# schematic.net
KiCad netlist of a schematic drawn in EAGLE
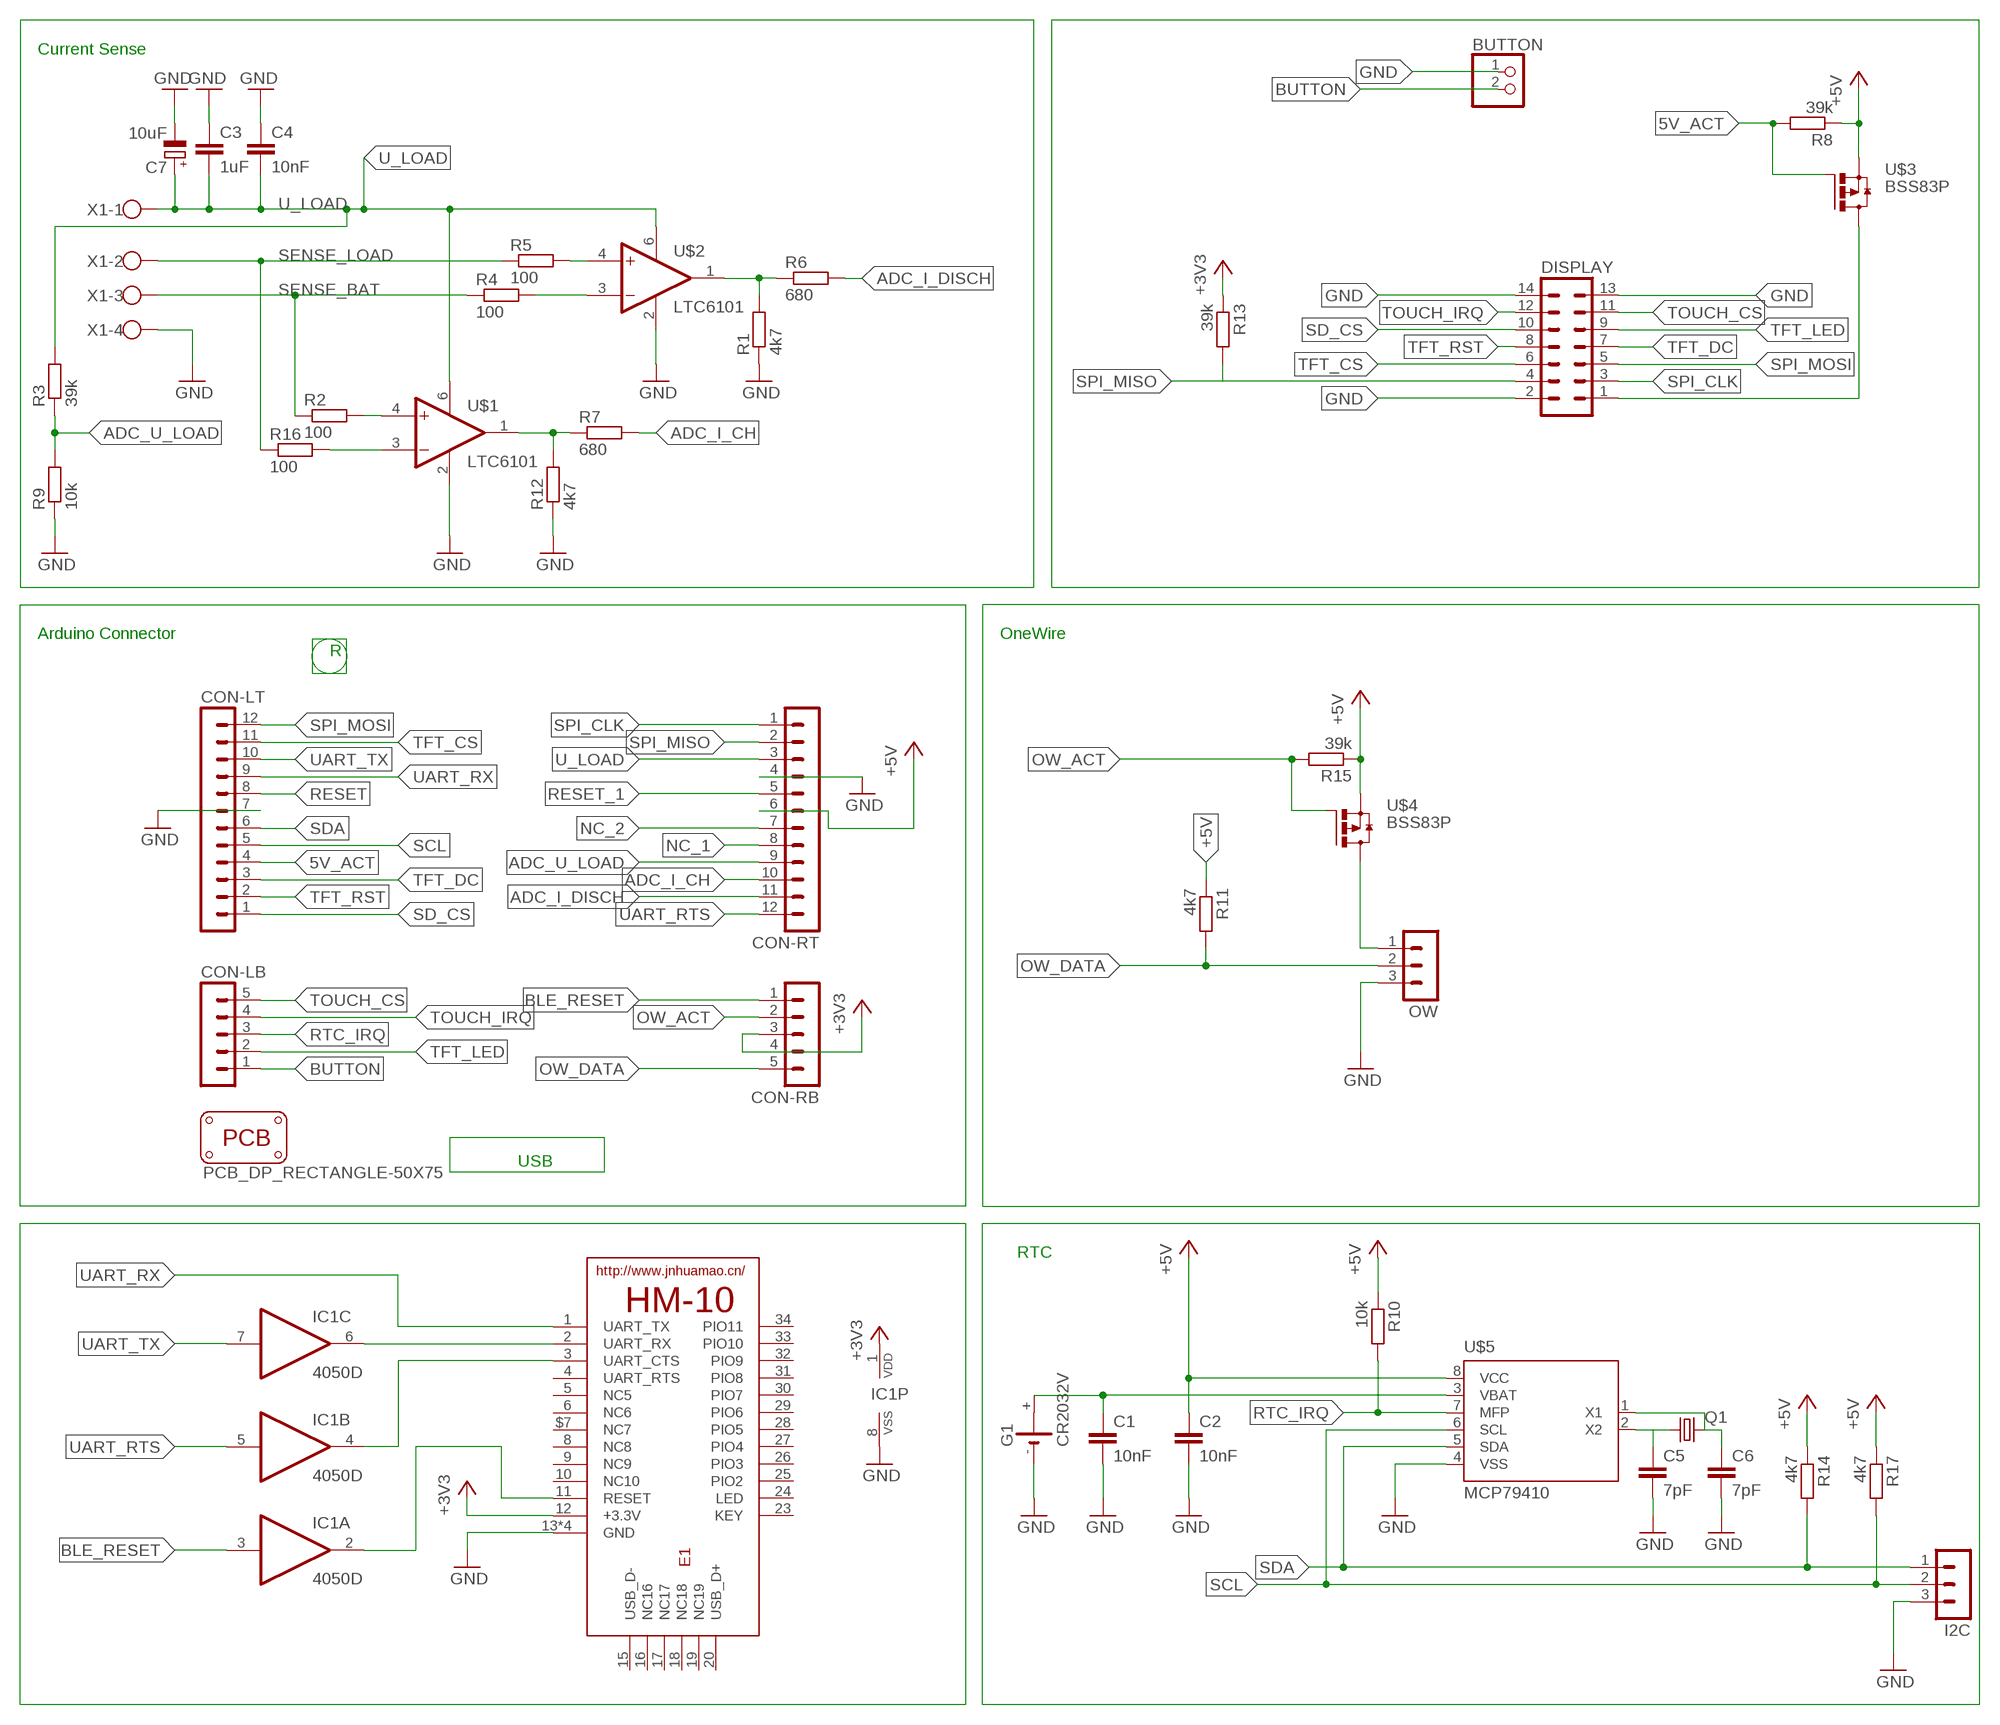
[diagram p0: schematic, sheet 1]

(export (version "E")
  (design (tool "Eeschema 10.0.6"))
  (components
    (comp (ref "BUTTON")
      (value "PINHD-1X2")
      (footprint "eagle-import:1X02")
      (libsource (lib "eagle-import") (part "PINHD-1X2"))
    )
    (comp (ref "C1")
      (value "10nF")
      (footprint "eagle-import:C1206")
      (libsource (lib "eagle-import") (part "C-EUC1206"))
    )
    (comp (ref "C2")
      (value "10nF")
      (footprint "eagle-import:C1206")
      (libsource (lib "eagle-import") (part "C-EUC1206"))
    )
    (comp (ref "C3")
      (value "1uF")
      (footprint "eagle-import:C1206")
      (libsource (lib "eagle-import") (part "C-EUC1206"))
    )
    (comp (ref "C4")
      (value "10nF")
      (footprint "eagle-import:C1206")
      (libsource (lib "eagle-import") (part "C-EUC1206"))
    )
    (comp (ref "C5")
      (value "7pF")
      (footprint "eagle-import:C1206")
      (libsource (lib "eagle-import") (part "C-EUC1206"))
    )
    (comp (ref "C6")
      (value "7pF")
      (footprint "eagle-import:C1206")
      (libsource (lib "eagle-import") (part "C-EUC1206"))
    )
    (comp (ref "C7")
      (value "10uF")
      (footprint "eagle-import:PANASONIC_B")
      (libsource (lib "eagle-import") (part "CPOL-EUB"))
    )
    (comp (ref "CON-LB")
      (value "MA05-1")
      (footprint "eagle-import:MA05-1")
      (libsource (lib "eagle-import") (part "MA05-1"))
    )
    (comp (ref "CON-LT")
      (value "MA12-1")
      (footprint "eagle-import:MA12-1")
      (libsource (lib "eagle-import") (part "MA12-1"))
    )
    (comp (ref "CON-RB")
      (value "MA05-1")
      (footprint "eagle-import:MA05-1")
      (libsource (lib "eagle-import") (part "MA05-1"))
    )
    (comp (ref "CON-RT")
      (value "MA12-1")
      (footprint "eagle-import:MA12-1")
      (libsource (lib "eagle-import") (part "MA12-1"))
    )
    (comp (ref "DISPLAY")
      (value "MA07-2")
      (footprint "eagle-import:MA07-2")
      (libsource (lib "eagle-import") (part "MA07-2"))
    )
    (comp (ref "E1")
      (value "HM-10-BOARD")
      (footprint "eagle-import:26.9X13X2.2_BOARD")
      (libsource (lib "eagle-import") (part "HM-10-BOARD"))
    )
    (comp (ref "G1")
      (value "CR2032V")
      (footprint "eagle-import:CR2032V")
      (libsource (lib "eagle-import") (part "CR2032V"))
    )
    (comp (ref "I2C")
      (value "MA03-1")
      (footprint "eagle-import:MA03-1")
      (libsource (lib "eagle-import") (part "MA03-1"))
    )
    (comp (ref "IC1")
      (value "4050D")
      (footprint "eagle-import:SO16")
      (libsource (lib "eagle-import") (part "4050D"))
    )
    (comp (ref "OW")
      (value "MA03-1")
      (footprint "eagle-import:MA03-1")
      (libsource (lib "eagle-import") (part "MA03-1"))
    )
    (comp (ref "PCB1")
      (value "PCB_DP_RECTANGLE-50X75")
      (footprint "eagle-import:DP5075_V1")
      (libsource (lib "eagle-import") (part "PCB_DP_RECTANGLE-50X75"))
    )
    (comp (ref "Q1")
      (value "CRYSTALTC26H")
      (footprint "eagle-import:TC26H")
      (libsource (lib "eagle-import") (part "CRYSTALTC26H"))
    )
    (comp (ref "R1")
      (value "4k7")
      (footprint "eagle-import:R1206")
      (libsource (lib "eagle-import") (part "R-EU_R1206"))
    )
    (comp (ref "R2")
      (value "100")
      (footprint "eagle-import:R1206")
      (libsource (lib "eagle-import") (part "R-EU_R1206"))
    )
    (comp (ref "R3")
      (value "39k")
      (footprint "eagle-import:R1206")
      (libsource (lib "eagle-import") (part "R-EU_R1206"))
    )
    (comp (ref "R4")
      (value "100")
      (footprint "eagle-import:R1206")
      (libsource (lib "eagle-import") (part "R-EU_R1206"))
    )
    (comp (ref "R5")
      (value "100")
      (footprint "eagle-import:R1206")
      (libsource (lib "eagle-import") (part "R-EU_R1206"))
    )
    (comp (ref "R6")
      (value "680")
      (footprint "eagle-import:R1206")
      (libsource (lib "eagle-import") (part "R-EU_R1206"))
    )
    (comp (ref "R7")
      (value "680")
      (footprint "eagle-import:R1206")
      (libsource (lib "eagle-import") (part "R-EU_R1206"))
    )
    (comp (ref "R8")
      (value "39k")
      (footprint "eagle-import:R1206")
      (libsource (lib "eagle-import") (part "R-EU_R1206"))
    )
    (comp (ref "R9")
      (value "10k")
      (footprint "eagle-import:R1206")
      (libsource (lib "eagle-import") (part "R-EU_R1206"))
    )
    (comp (ref "R10")
      (value "10k")
      (footprint "eagle-import:R1206")
      (libsource (lib "eagle-import") (part "R-EU_R1206"))
    )
    (comp (ref "R11")
      (value "4k7")
      (footprint "eagle-import:R1206")
      (libsource (lib "eagle-import") (part "R-EU_R1206"))
    )
    (comp (ref "R12")
      (value "4k7")
      (footprint "eagle-import:R1206")
      (libsource (lib "eagle-import") (part "R-EU_R1206"))
    )
    (comp (ref "R13")
      (value "39k")
      (footprint "eagle-import:R1206")
      (libsource (lib "eagle-import") (part "R-EU_R1206"))
    )
    (comp (ref "R14")
      (value "4k7")
      (footprint "eagle-import:R1206")
      (libsource (lib "eagle-import") (part "R-EU_R1206"))
    )
    (comp (ref "R15")
      (value "39k")
      (footprint "eagle-import:R1206")
      (libsource (lib "eagle-import") (part "R-EU_R1206"))
    )
    (comp (ref "R16")
      (value "100")
      (footprint "eagle-import:R1206")
      (libsource (lib "eagle-import") (part "R-EU_R1206"))
    )
    (comp (ref "R17")
      (value "4k7")
      (footprint "eagle-import:R1206")
      (libsource (lib "eagle-import") (part "R-EU_R1206"))
    )
    (comp (ref "U$1")
      (value "LTC6101")
      (footprint "eagle-import:TSOT23-6")
      (libsource (lib "eagle-import") (part "LTC6101"))
    )
    (comp (ref "U$2")
      (value "LTC6101")
      (footprint "eagle-import:TSOT23-6")
      (libsource (lib "eagle-import") (part "LTC6101"))
    )
    (comp (ref "U$3")
      (value "BSS83P")
      (footprint "eagle-import:SOT23")
      (libsource (lib "eagle-import") (part "BSS83P"))
    )
    (comp (ref "U$4")
      (value "BSS83P")
      (footprint "eagle-import:SOT23")
      (libsource (lib "eagle-import") (part "BSS83P"))
    )
    (comp (ref "U$5")
      (value "MCP79410")
      (footprint "eagle-import:SOIC8")
      (libsource (lib "eagle-import") (part "MCP79410"))
    )
    (comp (ref "X1")
      (value "W237-4")
      (footprint "eagle-import:W237-4")
      (libsource (lib "eagle-import") (part "W237-4"))
    )
  )
  (nets
    (net (code "1") (name "+3V3") (class "Default")
      (node (ref "CON-RB") (pin "3") (pinfunction "3_3") (pintype "passive"))
      (node (ref "CON-RB") (pin "4") (pinfunction "4_4") (pintype "passive"))
      (node (ref "E1") (pin "12") (pinfunction "+3.3V_12") (pintype "bidirectional"))
      (node (ref "IC1") (pin "1") (pinfunction "VDD_1") (pintype "power_in"))
      (node (ref "R13") (pin "1") (pinfunction "1_1") (pintype "passive"))
    )
    (net (code "2") (name "+5V") (class "Default")
      (node (ref "C2") (pin "1") (pinfunction "1_1") (pintype "passive"))
      (node (ref "CON-RT") (pin "6") (pinfunction "6_6") (pintype "passive"))
      (node (ref "R10") (pin "1") (pinfunction "1_1") (pintype "passive"))
      (node (ref "R11") (pin "1") (pinfunction "1_1") (pintype "passive"))
      (node (ref "R14") (pin "1") (pinfunction "1_1") (pintype "passive"))
      (node (ref "R15") (pin "1") (pinfunction "1_1") (pintype "passive"))
      (node (ref "R17") (pin "1") (pinfunction "1_1") (pintype "passive"))
      (node (ref "R8") (pin "1") (pinfunction "1_1") (pintype "passive"))
      (node (ref "U$3") (pin "2") (pinfunction "S_2") (pintype "passive"))
      (node (ref "U$4") (pin "2") (pinfunction "S_2") (pintype "passive"))
      (node (ref "U$5") (pin "8") (pinfunction "VCC_8") (pintype "power_in"))
    )
    (net (code "3") (name "/SENSE_BAT") (class "Default")
      (node (ref "R2") (pin "1") (pinfunction "1_1") (pintype "passive"))
      (node (ref "R4") (pin "1") (pinfunction "1_1") (pintype "passive"))
      (node (ref "X1") (pin "3") (pinfunction "KL_3") (pintype "passive"))
    )
    (net (code "4") (name "/SENSE_LOAD") (class "Default")
      (node (ref "R16") (pin "1") (pinfunction "1_1") (pintype "passive"))
      (node (ref "R5") (pin "1") (pinfunction "1_1") (pintype "passive"))
      (node (ref "X1") (pin "2") (pinfunction "KL_2") (pintype "passive"))
    )
    (net (code "5") (name "5V_ACT") (class "Default")
      (node (ref "CON-LT") (pin "4") (pinfunction "4_4") (pintype "passive"))
      (node (ref "R8") (pin "2") (pinfunction "2_2") (pintype "passive"))
      (node (ref "U$3") (pin "1") (pinfunction "G_1") (pintype "passive"))
    )
    (net (code "6") (name "ADC_I_CH") (class "Default")
      (node (ref "CON-RT") (pin "10") (pinfunction "10_10") (pintype "passive"))
      (node (ref "R7") (pin "2") (pinfunction "2_2") (pintype "passive"))
    )
    (net (code "7") (name "ADC_I_DISCH") (class "Default")
      (node (ref "CON-RT") (pin "11") (pinfunction "11_11") (pintype "passive"))
      (node (ref "R6") (pin "2") (pinfunction "2_2") (pintype "passive"))
    )
    (net (code "8") (name "ADC_U_LOAD") (class "Default")
      (node (ref "CON-RT") (pin "9") (pinfunction "9_9") (pintype "passive"))
      (node (ref "R3") (pin "1") (pinfunction "1_1") (pintype "passive"))
      (node (ref "R9") (pin "2") (pinfunction "2_2") (pintype "passive"))
    )
    (net (code "9") (name "BLE_RESET") (class "Default")
      (node (ref "CON-RB") (pin "1") (pinfunction "1_1") (pintype "passive"))
      (node (ref "IC1") (pin "3") (pinfunction "I_3") (pintype "input"))
    )
    (net (code "10") (name "BUTTON") (class "Default")
      (node (ref "BUTTON") (pin "2") (pinfunction "2_2") (pintype "passive"))
      (node (ref "CON-LB") (pin "1") (pinfunction "1_1") (pintype "passive"))
    )
    (net (code "11") (name "GND") (class "Default")
      (node (ref "BUTTON") (pin "1") (pinfunction "1_1") (pintype "passive"))
      (node (ref "C1") (pin "2") (pinfunction "2_2") (pintype "passive"))
      (node (ref "C2") (pin "2") (pinfunction "2_2") (pintype "passive"))
      (node (ref "C3") (pin "1") (pinfunction "1_1") (pintype "passive"))
      (node (ref "C4") (pin "1") (pinfunction "1_1") (pintype "passive"))
      (node (ref "C5") (pin "2") (pinfunction "2_2") (pintype "passive"))
      (node (ref "C6") (pin "2") (pinfunction "2_2") (pintype "passive"))
      (node (ref "C7") (pin "-") (pinfunction "-_-") (pintype "passive"))
      (node (ref "CON-LT") (pin "7") (pinfunction "7_7") (pintype "passive"))
      (node (ref "CON-RT") (pin "4") (pinfunction "4_4") (pintype "passive"))
      (node (ref "DISPLAY") (pin "13") (pinfunction "13_13") (pintype "passive"))
      (node (ref "DISPLAY") (pin "14") (pinfunction "14_14") (pintype "passive"))
      (node (ref "DISPLAY") (pin "2") (pinfunction "2_2") (pintype "passive"))
      (node (ref "E1") (pin "13") (pinfunction "GND_13") (pintype "bidirectional"))
      (node (ref "E1") (pin "14") (pinfunction "GND_14") (pintype "bidirectional"))
      (node (ref "E1") (pin "21") (pinfunction "GND_21") (pintype "bidirectional"))
      (node (ref "E1") (pin "22") (pinfunction "GND_22") (pintype "bidirectional"))
      (node (ref "G1") (pin "-") (pinfunction "-_-") (pintype "passive"))
      (node (ref "I2C") (pin "3") (pinfunction "3_3") (pintype "passive"))
      (node (ref "IC1") (pin "8") (pinfunction "VSS_8") (pintype "power_in"))
      (node (ref "OW") (pin "3") (pinfunction "3_3") (pintype "passive"))
      (node (ref "R1") (pin "1") (pinfunction "1_1") (pintype "passive"))
      (node (ref "R12") (pin "1") (pinfunction "1_1") (pintype "passive"))
      (node (ref "R9") (pin "1") (pinfunction "1_1") (pintype "passive"))
      (node (ref "U$1") (pin "2") (pinfunction "V-_2") (pintype "bidirectional"))
      (node (ref "U$2") (pin "2") (pinfunction "V-_2") (pintype "bidirectional"))
      (node (ref "U$5") (pin "4") (pinfunction "VSS_4") (pintype "power_in"))
      (node (ref "X1") (pin "4") (pinfunction "KL_4") (pintype "passive"))
    )
    (net (code "12") (name "NC_1") (class "Default")
      (node (ref "CON-RT") (pin "8") (pinfunction "8_8") (pintype "passive"))
    )
    (net (code "13") (name "NC_2") (class "Default")
      (node (ref "CON-RT") (pin "7") (pinfunction "7_7") (pintype "passive"))
    )
    (net (code "14") (name "Net-(E1-RESET)") (class "Default")
      (node (ref "E1") (pin "11") (pinfunction "RESET_11") (pintype "bidirectional"))
      (node (ref "IC1") (pin "2") (pinfunction "O_2") (pintype "output"))
    )
    (net (code "15") (name "Net-(E1-UART_CTS)") (class "Default")
      (node (ref "E1") (pin "3") (pinfunction "UART_CTS_3") (pintype "bidirectional"))
      (node (ref "IC1") (pin "4") (pinfunction "O_4") (pintype "output"))
    )
    (net (code "16") (name "Net-(E1-UART_RX)") (class "Default")
      (node (ref "E1") (pin "2") (pinfunction "UART_RX_2") (pintype "bidirectional"))
      (node (ref "IC1") (pin "6") (pinfunction "O_6") (pintype "output"))
    )
    (net (code "17") (name "Net-(U$1-+IN)") (class "Default")
      (node (ref "R2") (pin "2") (pinfunction "2_2") (pintype "passive"))
      (node (ref "U$1") (pin "4") (pinfunction "+IN_4") (pintype "bidirectional"))
    )
    (net (code "18") (name "Net-(U$1--IN)") (class "Default")
      (node (ref "R16") (pin "2") (pinfunction "2_2") (pintype "passive"))
      (node (ref "U$1") (pin "3") (pinfunction "-IN_3") (pintype "bidirectional"))
    )
    (net (code "19") (name "Net-(U$1-OUT1)") (class "Default")
      (node (ref "R12") (pin "2") (pinfunction "2_2") (pintype "passive"))
      (node (ref "R7") (pin "1") (pinfunction "1_1") (pintype "passive"))
      (node (ref "U$1") (pin "1") (pinfunction "OUT1_1") (pintype "bidirectional"))
    )
    (net (code "20") (name "Net-(U$2-+IN)") (class "Default")
      (node (ref "R5") (pin "2") (pinfunction "2_2") (pintype "passive"))
      (node (ref "U$2") (pin "4") (pinfunction "+IN_4") (pintype "bidirectional"))
    )
    (net (code "21") (name "Net-(U$2--IN)") (class "Default")
      (node (ref "R4") (pin "2") (pinfunction "2_2") (pintype "passive"))
      (node (ref "U$2") (pin "3") (pinfunction "-IN_3") (pintype "bidirectional"))
    )
    (net (code "22") (name "Net-(U$2-OUT1)") (class "Default")
      (node (ref "R1") (pin "2") (pinfunction "2_2") (pintype "passive"))
      (node (ref "R6") (pin "1") (pinfunction "1_1") (pintype "passive"))
      (node (ref "U$2") (pin "1") (pinfunction "OUT1_1") (pintype "bidirectional"))
    )
    (net (code "23") (name "Net-(U$3-D)") (class "Default")
      (node (ref "DISPLAY") (pin "1") (pinfunction "1_1") (pintype "passive"))
      (node (ref "U$3") (pin "3") (pinfunction "D_3") (pintype "passive"))
    )
    (net (code "24") (name "Net-(U$4-D)") (class "Default")
      (node (ref "OW") (pin "1") (pinfunction "1_1") (pintype "passive"))
      (node (ref "U$4") (pin "3") (pinfunction "D_3") (pintype "passive"))
    )
    (net (code "25") (name "Net-(U$5-VBAT)") (class "Default")
      (node (ref "C1") (pin "1") (pinfunction "1_1") (pintype "passive"))
      (node (ref "G1") (pin "+") (pinfunction "+_+") (pintype "passive"))
      (node (ref "U$5") (pin "3") (pinfunction "VBAT_3") (pintype "input"))
    )
    (net (code "26") (name "Net-(U$5-X1)") (class "Default")
      (node (ref "C6") (pin "1") (pinfunction "1_1") (pintype "passive"))
      (node (ref "Q1") (pin "2") (pinfunction "2_2") (pintype "passive"))
      (node (ref "U$5") (pin "1") (pinfunction "X1_1") (pintype "input"))
    )
    (net (code "27") (name "Net-(U$5-X2)") (class "Default")
      (node (ref "C5") (pin "1") (pinfunction "1_1") (pintype "passive"))
      (node (ref "Q1") (pin "1") (pinfunction "1_1") (pintype "passive"))
      (node (ref "U$5") (pin "2") (pinfunction "X2_2") (pintype "input"))
    )
    (net (code "28") (name "OW_ACT") (class "Default")
      (node (ref "CON-RB") (pin "2") (pinfunction "2_2") (pintype "passive"))
      (node (ref "R15") (pin "2") (pinfunction "2_2") (pintype "passive"))
      (node (ref "U$4") (pin "1") (pinfunction "G_1") (pintype "passive"))
    )
    (net (code "29") (name "OW_DATA") (class "Default")
      (node (ref "CON-RB") (pin "5") (pinfunction "5_5") (pintype "passive"))
      (node (ref "OW") (pin "2") (pinfunction "2_2") (pintype "passive"))
      (node (ref "R11") (pin "2") (pinfunction "2_2") (pintype "passive"))
    )
    (net (code "30") (name "RESET") (class "Default")
      (node (ref "CON-LT") (pin "8") (pinfunction "8_8") (pintype "passive"))
    )
    (net (code "31") (name "RESET_1") (class "Default")
      (node (ref "CON-RT") (pin "5") (pinfunction "5_5") (pintype "passive"))
    )
    (net (code "32") (name "RTC_IRQ") (class "Default")
      (node (ref "CON-LB") (pin "3") (pinfunction "3_3") (pintype "passive"))
      (node (ref "R10") (pin "2") (pinfunction "2_2") (pintype "passive"))
      (node (ref "U$5") (pin "7") (pinfunction "MFP_7") (pintype "output"))
    )
    (net (code "33") (name "SCL") (class "Default")
      (node (ref "CON-LT") (pin "5") (pinfunction "5_5") (pintype "passive"))
      (node (ref "I2C") (pin "2") (pinfunction "2_2") (pintype "passive"))
      (node (ref "R17") (pin "2") (pinfunction "2_2") (pintype "passive"))
      (node (ref "U$5") (pin "6") (pinfunction "SCL_6") (pintype "input"))
    )
    (net (code "34") (name "SDA") (class "Default")
      (node (ref "CON-LT") (pin "6") (pinfunction "6_6") (pintype "passive"))
      (node (ref "I2C") (pin "1") (pinfunction "1_1") (pintype "passive"))
      (node (ref "R14") (pin "2") (pinfunction "2_2") (pintype "passive"))
      (node (ref "U$5") (pin "5") (pinfunction "SDA_5") (pintype "bidirectional"))
    )
    (net (code "35") (name "SD_CS") (class "Default")
      (node (ref "CON-LT") (pin "1") (pinfunction "1_1") (pintype "passive"))
      (node (ref "DISPLAY") (pin "10") (pinfunction "10_10") (pintype "passive"))
    )
    (net (code "36") (name "SPI_CLK") (class "Default")
      (node (ref "CON-RT") (pin "1") (pinfunction "1_1") (pintype "passive"))
      (node (ref "DISPLAY") (pin "3") (pinfunction "3_3") (pintype "passive"))
    )
    (net (code "37") (name "SPI_MISO") (class "Default")
      (node (ref "CON-RT") (pin "2") (pinfunction "2_2") (pintype "passive"))
      (node (ref "DISPLAY") (pin "4") (pinfunction "4_4") (pintype "passive"))
      (node (ref "R13") (pin "2") (pinfunction "2_2") (pintype "passive"))
    )
    (net (code "38") (name "SPI_MOSI") (class "Default")
      (node (ref "CON-LT") (pin "12") (pinfunction "12_12") (pintype "passive"))
      (node (ref "DISPLAY") (pin "5") (pinfunction "5_5") (pintype "passive"))
    )
    (net (code "39") (name "TFT_CS") (class "Default")
      (node (ref "CON-LT") (pin "11") (pinfunction "11_11") (pintype "passive"))
      (node (ref "DISPLAY") (pin "6") (pinfunction "6_6") (pintype "passive"))
    )
    (net (code "40") (name "TFT_DC") (class "Default")
      (node (ref "CON-LT") (pin "3") (pinfunction "3_3") (pintype "passive"))
      (node (ref "DISPLAY") (pin "7") (pinfunction "7_7") (pintype "passive"))
    )
    (net (code "41") (name "TFT_LED") (class "Default")
      (node (ref "CON-LB") (pin "2") (pinfunction "2_2") (pintype "passive"))
      (node (ref "DISPLAY") (pin "9") (pinfunction "9_9") (pintype "passive"))
    )
    (net (code "42") (name "TFT_RST") (class "Default")
      (node (ref "CON-LT") (pin "2") (pinfunction "2_2") (pintype "passive"))
      (node (ref "DISPLAY") (pin "8") (pinfunction "8_8") (pintype "passive"))
    )
    (net (code "43") (name "TOUCH_CS") (class "Default")
      (node (ref "CON-LB") (pin "5") (pinfunction "5_5") (pintype "passive"))
      (node (ref "DISPLAY") (pin "11") (pinfunction "11_11") (pintype "passive"))
    )
    (net (code "44") (name "TOUCH_IRQ") (class "Default")
      (node (ref "CON-LB") (pin "4") (pinfunction "4_4") (pintype "passive"))
      (node (ref "DISPLAY") (pin "12") (pinfunction "12_12") (pintype "passive"))
    )
    (net (code "45") (name "UART_RTS") (class "Default")
      (node (ref "CON-RT") (pin "12") (pinfunction "12_12") (pintype "passive"))
      (node (ref "IC1") (pin "5") (pinfunction "I_5") (pintype "input"))
    )
    (net (code "46") (name "UART_RX") (class "Default")
      (node (ref "CON-LT") (pin "9") (pinfunction "9_9") (pintype "passive"))
      (node (ref "E1") (pin "1") (pinfunction "UART_TX_1") (pintype "bidirectional"))
    )
    (net (code "47") (name "UART_TX") (class "Default")
      (node (ref "CON-LT") (pin "10") (pinfunction "10_10") (pintype "passive"))
      (node (ref "IC1") (pin "7") (pinfunction "I_7") (pintype "input"))
    )
    (net (code "48") (name "U_LOAD") (class "Default")
      (node (ref "C3") (pin "2") (pinfunction "2_2") (pintype "passive"))
      (node (ref "C4") (pin "2") (pinfunction "2_2") (pintype "passive"))
      (node (ref "C7") (pin "+") (pinfunction "+_+") (pintype "passive"))
      (node (ref "CON-RT") (pin "3") (pinfunction "3_3") (pintype "passive"))
      (node (ref "R3") (pin "2") (pinfunction "2_2") (pintype "passive"))
      (node (ref "U$1") (pin "6") (pinfunction "V+_6") (pintype "bidirectional"))
      (node (ref "U$2") (pin "6") (pinfunction "V+_6") (pintype "bidirectional"))
      (node (ref "X1") (pin "1") (pinfunction "KL_1") (pintype "passive"))
    )
    (net (code "49") (name "unconnected-(E1-KEY-Pad23)") (class "Default")
      (node (ref "E1") (pin "23") (pinfunction "KEY_23") (pintype "bidirectional"))
    )
    (net (code "50") (name "unconnected-(E1-LED-Pad24)") (class "Default")
      (node (ref "E1") (pin "24") (pinfunction "LED_24") (pintype "bidirectional"))
    )
    (net (code "51") (name "unconnected-(E1-NC5-Pad5)") (class "Default")
      (node (ref "E1") (pin "5") (pinfunction "NC5_5") (pintype "bidirectional"))
    )
    (net (code "52") (name "unconnected-(E1-NC6-Pad6)") (class "Default")
      (node (ref "E1") (pin "6") (pinfunction "NC6_6") (pintype "bidirectional"))
    )
    (net (code "53") (name "unconnected-(E1-NC7-Pad$7)") (class "Default")
      (node (ref "E1") (pin "$7") (pinfunction "NC7_$7") (pintype "bidirectional"))
    )
    (net (code "54") (name "unconnected-(E1-NC8-Pad8)") (class "Default")
      (node (ref "E1") (pin "8") (pinfunction "NC8_8") (pintype "bidirectional"))
    )
    (net (code "55") (name "unconnected-(E1-NC9-Pad9)") (class "Default")
      (node (ref "E1") (pin "9") (pinfunction "NC9_9") (pintype "bidirectional"))
    )
    (net (code "56") (name "unconnected-(E1-NC10-Pad10)") (class "Default")
      (node (ref "E1") (pin "10") (pinfunction "NC10_10") (pintype "bidirectional"))
    )
    (net (code "57") (name "unconnected-(E1-NC16-Pad16)") (class "Default")
      (node (ref "E1") (pin "16") (pinfunction "NC16_16") (pintype "bidirectional"))
    )
    (net (code "58") (name "unconnected-(E1-NC17-Pad17)") (class "Default")
      (node (ref "E1") (pin "17") (pinfunction "NC17_17") (pintype "bidirectional"))
    )
    (net (code "59") (name "unconnected-(E1-NC18-Pad18)") (class "Default")
      (node (ref "E1") (pin "18") (pinfunction "NC18_18") (pintype "bidirectional"))
    )
    (net (code "60") (name "unconnected-(E1-NC19-Pad19)") (class "Default")
      (node (ref "E1") (pin "19") (pinfunction "NC19_19") (pintype "bidirectional"))
    )
    (net (code "61") (name "unconnected-(E1-PIO2-Pad25)") (class "Default")
      (node (ref "E1") (pin "25") (pinfunction "PIO2_25") (pintype "bidirectional"))
    )
    (net (code "62") (name "unconnected-(E1-PIO3-Pad26)") (class "Default")
      (node (ref "E1") (pin "26") (pinfunction "PIO3_26") (pintype "bidirectional"))
    )
    (net (code "63") (name "unconnected-(E1-PIO4-Pad27)") (class "Default")
      (node (ref "E1") (pin "27") (pinfunction "PIO4_27") (pintype "bidirectional"))
    )
    (net (code "64") (name "unconnected-(E1-PIO5-Pad28)") (class "Default")
      (node (ref "E1") (pin "28") (pinfunction "PIO5_28") (pintype "bidirectional"))
    )
    (net (code "65") (name "unconnected-(E1-PIO6-Pad29)") (class "Default")
      (node (ref "E1") (pin "29") (pinfunction "PIO6_29") (pintype "bidirectional"))
    )
    (net (code "66") (name "unconnected-(E1-PIO7-Pad30)") (class "Default")
      (node (ref "E1") (pin "30") (pinfunction "PIO7_30") (pintype "bidirectional"))
    )
    (net (code "67") (name "unconnected-(E1-PIO8-Pad31)") (class "Default")
      (node (ref "E1") (pin "31") (pinfunction "PIO8_31") (pintype "bidirectional"))
    )
    (net (code "68") (name "unconnected-(E1-PIO9-Pad32)") (class "Default")
      (node (ref "E1") (pin "32") (pinfunction "PIO9_32") (pintype "bidirectional"))
    )
    (net (code "69") (name "unconnected-(E1-PIO10-Pad33)") (class "Default")
      (node (ref "E1") (pin "33") (pinfunction "PIO10_33") (pintype "bidirectional"))
    )
    (net (code "70") (name "unconnected-(E1-PIO11-Pad34)") (class "Default")
      (node (ref "E1") (pin "34") (pinfunction "PIO11_34") (pintype "bidirectional"))
    )
    (net (code "71") (name "unconnected-(E1-UART_RTS-Pad4)") (class "Default")
      (node (ref "E1") (pin "4") (pinfunction "UART_RTS_4") (pintype "bidirectional"))
    )
    (net (code "72") (name "unconnected-(E1-USB_D+-Pad20)") (class "Default")
      (node (ref "E1") (pin "20") (pinfunction "USB_D+_20") (pintype "bidirectional"))
    )
    (net (code "73") (name "unconnected-(E1-USB_D--Pad15)") (class "Default")
      (node (ref "E1") (pin "15") (pinfunction "USB_D-_15") (pintype "bidirectional"))
    )
    (net (code "74") (name "unconnected-(G1-+-Pad+@1)") (class "Default")
      (node (ref "G1") (pin "+@1") (pinfunction "+_+@1") (pintype "passive"))
    )
  )
)
